# Box_Light_NEW.net
KiCad netlist of a schematic drawn in EAGLE
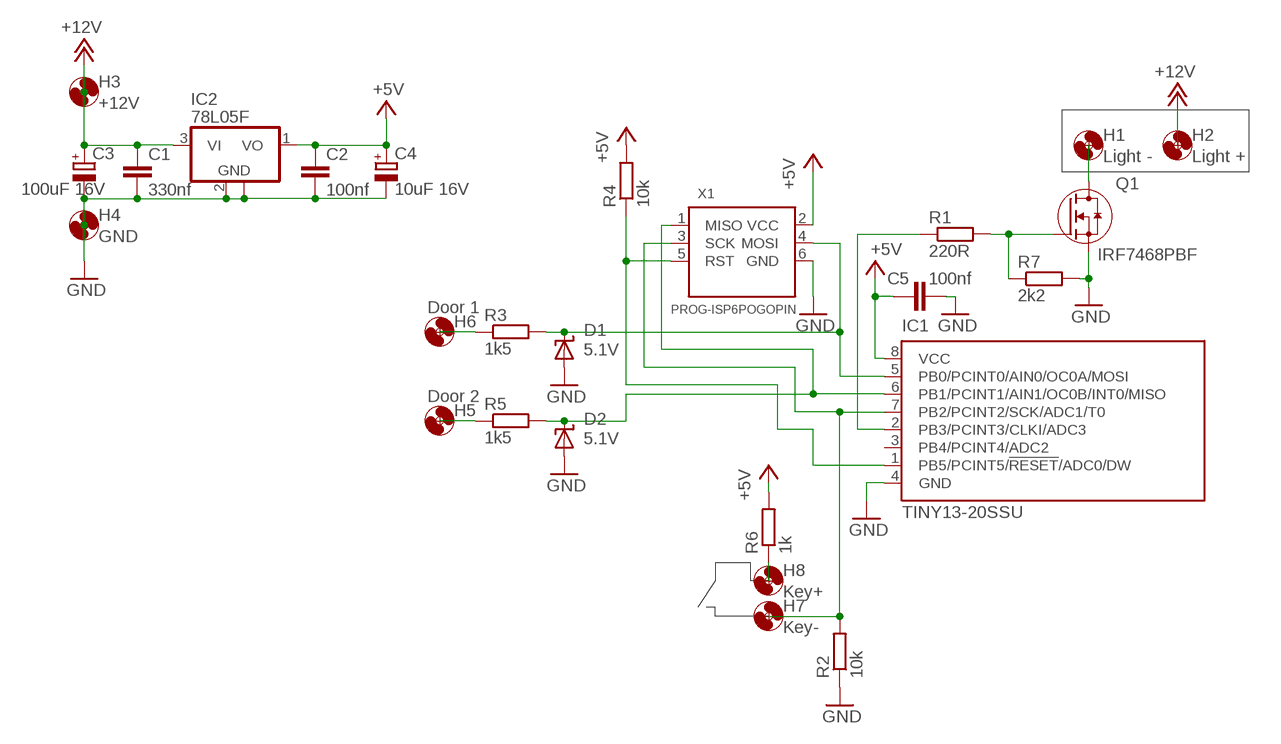
[diagram p0: schematic, sheet 1]

(export (version "E")
  (design (tool "Eeschema 10.0.6"))
  (components
    (comp (ref "C1")
      (value "330nf")
      (footprint "eagle-import:C0805")
      (libsource (lib "eagle-import") (part "C-EUC0805"))
    )
    (comp (ref "C2")
      (value "100nf")
      (footprint "eagle-import:C0805")
      (libsource (lib "eagle-import") (part "C-EUC0805"))
    )
    (comp (ref "C3")
      (value "100uF 16V")
      (footprint "eagle-import:SMC_C")
      (libsource (lib "eagle-import") (part "CPOL-EUSMCC"))
    )
    (comp (ref "C4")
      (value "10uF 16V")
      (footprint "eagle-import:SMC_B")
      (libsource (lib "eagle-import") (part "CPOL-EUSMCB"))
    )
    (comp (ref "C5")
      (value "100nf")
      (footprint "eagle-import:C0805")
      (libsource (lib "eagle-import") (part "C-EUC0805"))
    )
    (comp (ref "D1")
      (value "5.1V")
      (footprint "eagle-import:SOD123")
      (libsource (lib "eagle-import") (part "ZENER"))
    )
    (comp (ref "D2")
      (value "5.1V")
      (footprint "eagle-import:SOD123")
      (libsource (lib "eagle-import") (part "ZENER"))
    )
    (comp (ref "H1")
      (value "Light -")
      (footprint "eagle-import:3,0")
      (libsource (lib "eagle-import") (part "MOUNT-HOLE3.0"))
    )
    (comp (ref "H2")
      (value "Light +")
      (footprint "eagle-import:3,0")
      (libsource (lib "eagle-import") (part "MOUNT-HOLE3.0"))
    )
    (comp (ref "H3")
      (value "+12V")
      (footprint "eagle-import:3,0")
      (libsource (lib "eagle-import") (part "MOUNT-HOLE3.0"))
    )
    (comp (ref "H4")
      (value "GND")
      (footprint "eagle-import:3,0")
      (libsource (lib "eagle-import") (part "MOUNT-HOLE3.0"))
    )
    (comp (ref "H5")
      (value "Door 2")
      (footprint "eagle-import:2,8")
      (libsource (lib "eagle-import") (part "MOUNT-HOLE2.8"))
    )
    (comp (ref "H6")
      (value "Door 1")
      (footprint "eagle-import:2,8")
      (libsource (lib "eagle-import") (part "MOUNT-HOLE2.8"))
    )
    (comp (ref "H7")
      (value "Key-")
      (footprint "eagle-import:2,8")
      (libsource (lib "eagle-import") (part "MOUNT-HOLE2.8"))
    )
    (comp (ref "H8")
      (value "Key+")
      (footprint "eagle-import:2,8")
      (libsource (lib "eagle-import") (part "MOUNT-HOLE2.8"))
    )
    (comp (ref "IC1")
      (value "TINY13-20SSU")
      (footprint "eagle-import:8S1")
      (fields (field (name "MPN") "ATTINY13-20SSU"))
      (libsource (lib "eagle-import") (part "TINY13SSU-20"))
    )
    (comp (ref "IC2")
      (value "78L05F")
      (footprint "eagle-import:SOT89")
      (libsource (lib "eagle-import") (part "78LF05"))
    )
    (comp (ref "Q1")
      (value "IRF7468PBF")
      (footprint "eagle-import:SO08")
      (libsource (lib "eagle-import") (part "IRF7468PBF"))
    )
    (comp (ref "R1")
      (value "220R")
      (footprint "eagle-import:R0805")
      (libsource (lib "eagle-import") (part "R-EU_R0805"))
    )
    (comp (ref "R2")
      (value "10k")
      (footprint "eagle-import:R0805")
      (libsource (lib "eagle-import") (part "R-EU_R0805"))
    )
    (comp (ref "R3")
      (value "1k5")
      (footprint "eagle-import:R0805")
      (libsource (lib "eagle-import") (part "R-EU_R0805"))
    )
    (comp (ref "R4")
      (value "10k")
      (footprint "eagle-import:R0805")
      (libsource (lib "eagle-import") (part "R-EU_R0805"))
    )
    (comp (ref "R5")
      (value "1k5")
      (footprint "eagle-import:R0805")
      (libsource (lib "eagle-import") (part "R-EU_R0805"))
    )
    (comp (ref "R6")
      (value "1k")
      (footprint "eagle-import:R0805")
      (libsource (lib "eagle-import") (part "R-EU_R0805"))
    )
    (comp (ref "R7")
      (value "2k2")
      (footprint "eagle-import:R0805")
      (libsource (lib "eagle-import") (part "R-EU_R0805"))
    )
    (comp (ref "X1")
      (value "PROG-ISP6POGOPIN")
      (footprint "eagle-import:PROG_POGOPIN")
      (libsource (lib "eagle-import") (part "PROG-ISP6POGOPIN"))
    )
  )
  (nets
    (net (code "1") (name "+5V") (class "Default")
      (node (ref "C2") (pin "1") (pinfunction "1_1") (pintype "passive"))
      (node (ref "C4") (pin "+") (pinfunction "+_+") (pintype "passive"))
      (node (ref "C5") (pin "1") (pinfunction "1_1") (pintype "passive"))
      (node (ref "IC1") (pin "8") (pinfunction "VCC_8") (pintype "power_in"))
      (node (ref "IC2") (pin "1") (pinfunction "VO_1") (pintype "passive"))
      (node (ref "R4") (pin "2") (pinfunction "2_2") (pintype "passive"))
      (node (ref "R6") (pin "2") (pinfunction "2_2") (pintype "passive"))
      (node (ref "X1") (pin "2") (pinfunction "VCC_2") (pintype "bidirectional"))
    )
    (net (code "2") (name "+12V") (class "Default")
      (node (ref "C1") (pin "1") (pinfunction "1_1") (pintype "passive"))
      (node (ref "C3") (pin "+") (pinfunction "+_+") (pintype "passive"))
      (node (ref "H2") (pin "P$1") (pinfunction "P$1_P$1") (pintype "bidirectional"))
      (node (ref "H3") (pin "P$1") (pinfunction "P$1_P$1") (pintype "bidirectional"))
      (node (ref "IC2") (pin "3") (pinfunction "VI_3") (pintype "input"))
    )
    (net (code "3") (name "GND") (class "Default")
      (node (ref "C1") (pin "2") (pinfunction "2_2") (pintype "passive"))
      (node (ref "C2") (pin "2") (pinfunction "2_2") (pintype "passive"))
      (node (ref "C3") (pin "-") (pinfunction "-_-") (pintype "passive"))
      (node (ref "C4") (pin "-") (pinfunction "-_-") (pintype "passive"))
      (node (ref "C5") (pin "2") (pinfunction "2_2") (pintype "passive"))
      (node (ref "D1") (pin "A") (pinfunction "A_A") (pintype "passive"))
      (node (ref "D2") (pin "A") (pinfunction "A_A") (pintype "passive"))
      (node (ref "H4") (pin "P$1") (pinfunction "P$1_P$1") (pintype "bidirectional"))
      (node (ref "IC1") (pin "4") (pinfunction "GND_4") (pintype "power_in"))
      (node (ref "IC2") (pin "2") (pinfunction "GND_2") (pintype "passive"))
      (node (ref "IC2") (pin "2@1") (pinfunction "GND_2@1") (pintype "passive"))
      (node (ref "Q1") (pin "1") (pinfunction "S_1") (pintype "passive"))
      (node (ref "Q1") (pin "2") (pinfunction "S_2") (pintype "passive"))
      (node (ref "Q1") (pin "3") (pinfunction "S_3") (pintype "passive"))
      (node (ref "R2") (pin "1") (pinfunction "1_1") (pintype "passive"))
      (node (ref "R7") (pin "2") (pinfunction "2_2") (pintype "passive"))
      (node (ref "X1") (pin "6") (pinfunction "GND_6") (pintype "power_in"))
    )
    (net (code "4") (name "Net-(H1-PadP$1)") (class "Default")
      (node (ref "H1") (pin "P$1") (pinfunction "P$1_P$1") (pintype "bidirectional"))
      (node (ref "Q1") (pin "5") (pinfunction "D_5") (pintype "passive"))
      (node (ref "Q1") (pin "6") (pinfunction "D_6") (pintype "passive"))
      (node (ref "Q1") (pin "7") (pinfunction "D_7") (pintype "passive"))
      (node (ref "Q1") (pin "8") (pinfunction "D_8") (pintype "passive"))
    )
    (net (code "5") (name "Net-(H5-PadP$1)") (class "Default")
      (node (ref "H5") (pin "P$1") (pinfunction "P$1_P$1") (pintype "bidirectional"))
      (node (ref "R5") (pin "1") (pinfunction "1_1") (pintype "passive"))
    )
    (net (code "6") (name "Net-(H6-PadP$1)") (class "Default")
      (node (ref "H6") (pin "P$1") (pinfunction "P$1_P$1") (pintype "bidirectional"))
      (node (ref "R3") (pin "1") (pinfunction "1_1") (pintype "passive"))
    )
    (net (code "7") (name "Net-(H8-PadP$1)") (class "Default")
      (node (ref "H8") (pin "P$1") (pinfunction "P$1_P$1") (pintype "bidirectional"))
      (node (ref "R6") (pin "1") (pinfunction "1_1") (pintype "passive"))
    )
    (net (code "8") (name "Net-(IC1-PB0{slash}PCINT0{slash}AIN0{slash}OC0A{slash}MOSI)") (class "Default")
      (node (ref "D1") (pin "C") (pinfunction "C_C") (pintype "passive"))
      (node (ref "IC1") (pin "5") (pinfunction "PB0/PCINT0/AIN0/OC0A/MOSI_5") (pintype "bidirectional"))
      (node (ref "R3") (pin "2") (pinfunction "2_2") (pintype "passive"))
      (node (ref "X1") (pin "4") (pinfunction "MOSI_4") (pintype "bidirectional"))
    )
    (net (code "9") (name "Net-(IC1-PB1{slash}PCINT1{slash}AIN1{slash}OC0B{slash}INT0{slash}MISO)") (class "Default")
      (node (ref "D2") (pin "C") (pinfunction "C_C") (pintype "passive"))
      (node (ref "IC1") (pin "6") (pinfunction "PB1/PCINT1/AIN1/OC0B/INT0/MISO_6") (pintype "bidirectional"))
      (node (ref "R5") (pin "2") (pinfunction "2_2") (pintype "passive"))
      (node (ref "X1") (pin "1") (pinfunction "MISO_1") (pintype "bidirectional"))
    )
    (net (code "10") (name "Net-(IC1-PB2{slash}PCINT2{slash}SCK{slash}ADC1{slash}T0)") (class "Default")
      (node (ref "H7") (pin "P$1") (pinfunction "P$1_P$1") (pintype "bidirectional"))
      (node (ref "IC1") (pin "7") (pinfunction "PB2/PCINT2/SCK/ADC1/T0_7") (pintype "bidirectional"))
      (node (ref "R2") (pin "2") (pinfunction "2_2") (pintype "passive"))
      (node (ref "X1") (pin "3") (pinfunction "SCK_3") (pintype "bidirectional"))
    )
    (net (code "11") (name "Net-(IC1-PB3{slash}PCINT3{slash}CLKI{slash}ADC3)") (class "Default")
      (node (ref "IC1") (pin "2") (pinfunction "PB3/PCINT3/CLKI/ADC3_2") (pintype "bidirectional"))
      (node (ref "R1") (pin "1") (pinfunction "1_1") (pintype "passive"))
    )
    (net (code "12") (name "Net-(IC1-PB5{slash}PCINT5{slash}~{RESET}{slash}ADC0{slash}DW)") (class "Default")
      (node (ref "IC1") (pin "1") (pinfunction "PB5/PCINT5/~{RESET}/ADC0/DW_1") (pintype "bidirectional"))
      (node (ref "R4") (pin "1") (pinfunction "1_1") (pintype "passive"))
      (node (ref "X1") (pin "5") (pinfunction "RST_5") (pintype "bidirectional"))
    )
    (net (code "13") (name "Net-(Q1-G)") (class "Default")
      (node (ref "Q1") (pin "4") (pinfunction "G_4") (pintype "passive"))
      (node (ref "R1") (pin "2") (pinfunction "2_2") (pintype "passive"))
      (node (ref "R7") (pin "1") (pinfunction "1_1") (pintype "passive"))
    )
    (net (code "14") (name "unconnected-(IC1-PB4{slash}PCINT4{slash}ADC2-Pad3)") (class "Default")
      (node (ref "IC1") (pin "3") (pinfunction "PB4/PCINT4/ADC2_3") (pintype "bidirectional"))
    )
  )
)
